# GILBERT.net
KiCad netlist of a schematic drawn in Altium Designer
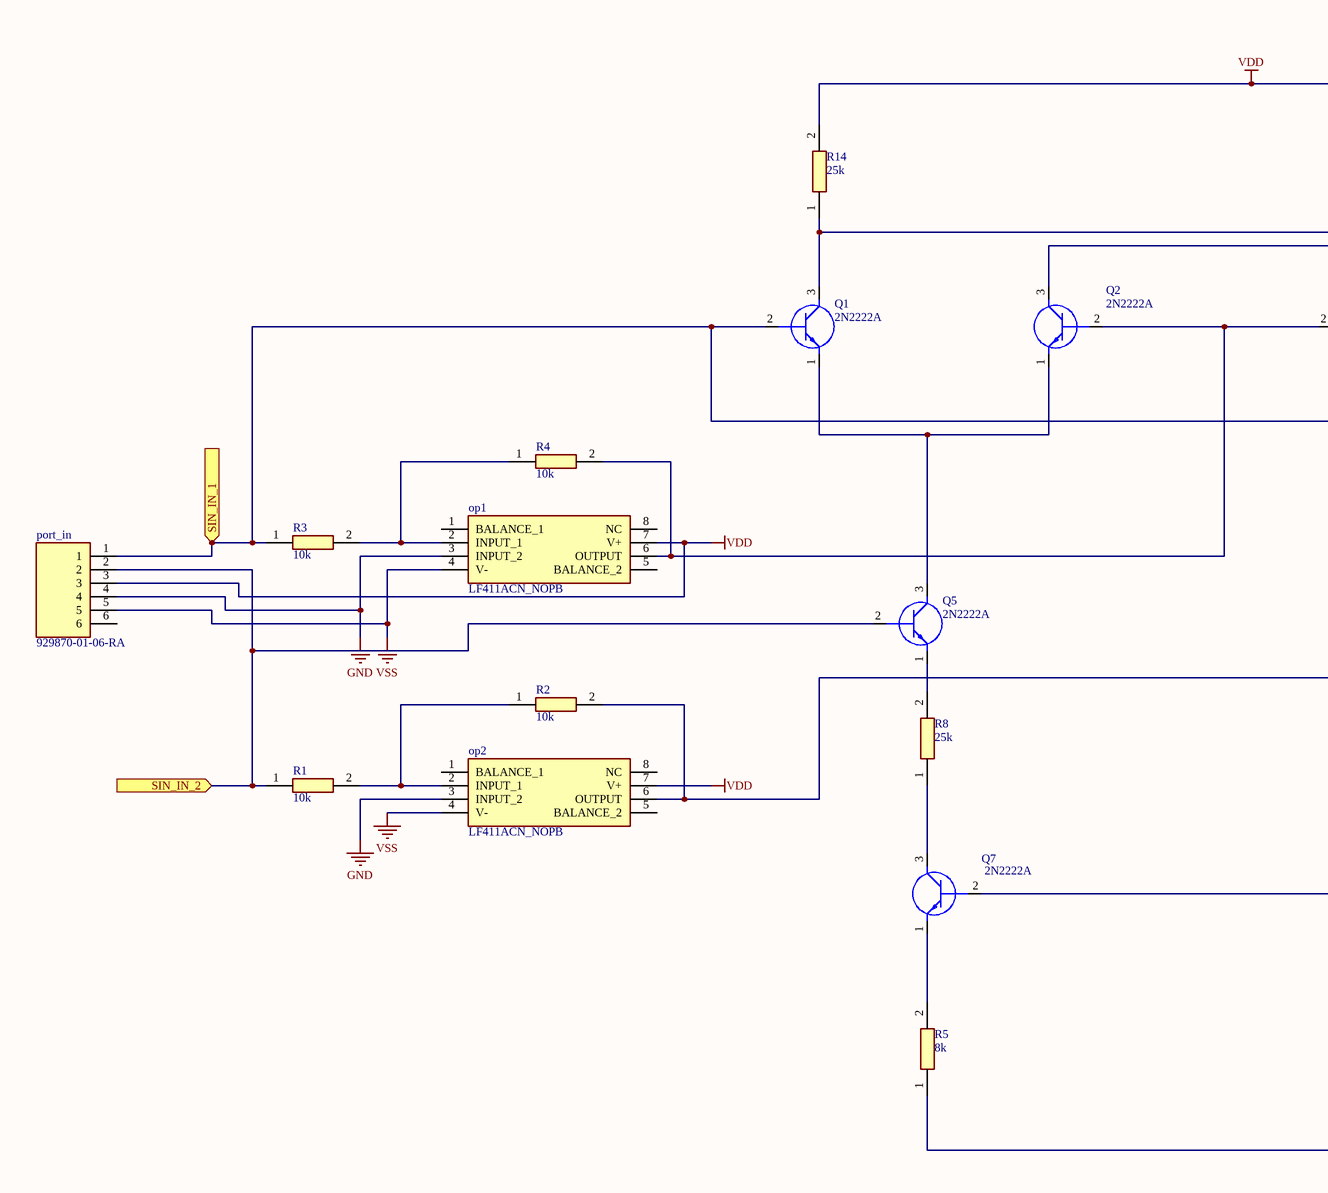
[diagram p0: GILBERT.SchDoc, left]
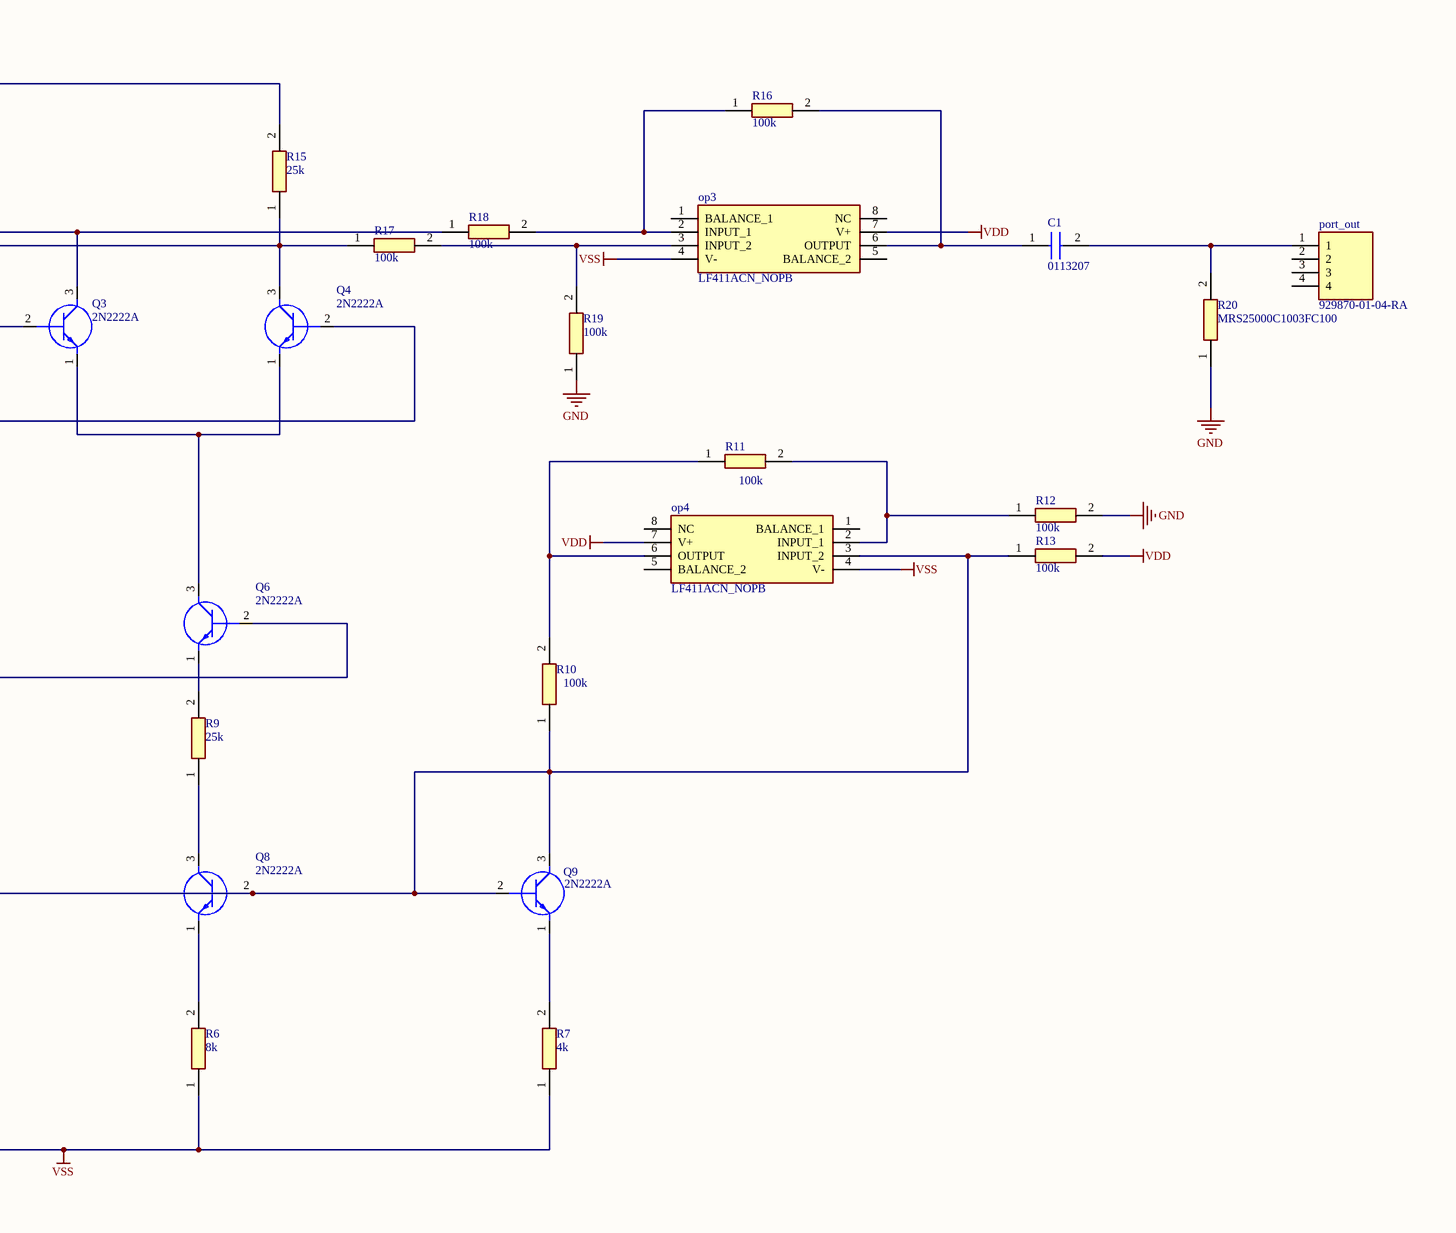
[diagram p1: GILBERT.SchDoc, right]

(export (version "E")
  (design (tool "Eeschema 10.0.6"))
  (components
    (comp (ref "C1")
      (value "0113207")
      (footprint "SamacSys:CAPPA2400W30L800D400")
      (description "Capacitor")
      (libsource (lib "SamacSys") (part "0113207"))
    )
    (comp (ref "op1")
      (value "LF411ACN_NOPB")
      (footprint "SamacSys:DIP794W53P254L959H508Q8N")
      (description "Integrated Circuit")
      (fields
        (field (name "MANUFACTURER_PART_NUMBER") "LF411ACN/NOPB")
        (field (name "MOUSER PART NUMBER") "926-LF411ACN/NOPB")
      )
      (libsource (lib "*") (part "LF411ACN_NOPB"))
    )
    (comp (ref "op2")
      (value "LF411ACN_NOPB")
      (footprint "SamacSys:DIP794W53P254L959H508Q8N")
      (description "Integrated Circuit")
      (fields
        (field (name "MANUFACTURER_PART_NUMBER") "LF411ACN/NOPB")
        (field (name "MOUSER PART NUMBER") "926-LF411ACN/NOPB")
      )
      (libsource (lib "SamacSys") (part "LF411ACN_NOPB"))
    )
    (comp (ref "op3")
      (value "LF411ACN_NOPB")
      (footprint "SamacSys:DIP794W53P254L959H508Q8N")
      (description "Integrated Circuit")
      (fields
        (field (name "MANUFACTURER_PART_NUMBER") "LF411ACN/NOPB")
        (field (name "MOUSER PART NUMBER") "926-LF411ACN/NOPB")
      )
      (libsource (lib "SamacSys") (part "LF411ACN_NOPB"))
    )
    (comp (ref "op4")
      (value "LF411ACN_NOPB")
      (footprint "SamacSys:DIP794W53P254L959H508Q8N")
      (description "Integrated Circuit")
      (fields
        (field (name "MANUFACTURER_PART_NUMBER") "LF411ACN/NOPB")
        (field (name "MOUSER PART NUMBER") "926-LF411ACN/NOPB")
      )
      (libsource (lib "") (part "LF411ACN_NOPB_1"))
    )
    (comp (ref "port_in")
      (value "929870-01-06-RA")
      (footprint "SamacSys:RHDR6W64P0X254_1X6_1524X254X380P")
      (description "Connector")
      (fields (field (name "MOUSER PART NUMBER") "517-929870-01-06-RA"))
      (libsource (lib "SamacSys") (part "929870-01-06-RA"))
    )
    (comp (ref "port_out")
      (value "929870-01-04-RA")
      (footprint "SamacSys:RHDR4W76P0X254_1X4_1016X254X826P")
      (description "Connector")
      (fields (field (name "MOUSER PART NUMBER") "517-929870-01-04-RA"))
      (libsource (lib "SamacSys") (part "929870-01-04-RA"))
    )
    (comp (ref "Q1")
      (value "2N2222A")
      (footprint "SamacSys:CENTRAL_TO18")
      (description "Transistor BJT NPN")
      (fields (field (name "MOUSER PART NUMBER") "610-2N2222A"))
      (libsource (lib "SamacSys") (part "2N2222A"))
    )
    (comp (ref "Q2")
      (value "2N2222A")
      (footprint "SamacSys:CENTRAL_TO18")
      (description "Transistor BJT NPN")
      (fields (field (name "MOUSER PART NUMBER") "610-2N2222A"))
      (libsource (lib "SamacSys") (part "2N2222A"))
    )
    (comp (ref "Q3")
      (value "2N2222A")
      (footprint "SamacSys:CENTRAL_TO18")
      (description "Transistor BJT NPN")
      (fields (field (name "MOUSER PART NUMBER") "610-2N2222A"))
      (libsource (lib "SamacSys") (part "2N2222A"))
    )
    (comp (ref "Q4")
      (value "2N2222A")
      (footprint "SamacSys:CENTRAL_TO18")
      (description "Transistor BJT NPN")
      (fields (field (name "MOUSER PART NUMBER") "610-2N2222A"))
      (libsource (lib "SamacSys") (part "2N2222A"))
    )
    (comp (ref "Q5")
      (value "2N2222A")
      (footprint "SamacSys:CENTRAL_TO18")
      (description "Transistor BJT NPN")
      (fields (field (name "MOUSER PART NUMBER") "610-2N2222A"))
      (libsource (lib "SamacSys") (part "2N2222A"))
    )
    (comp (ref "Q6")
      (value "2N2222A")
      (footprint "SamacSys:CENTRAL_TO18")
      (description "Transistor BJT NPN")
      (fields (field (name "MOUSER PART NUMBER") "610-2N2222A"))
      (libsource (lib "SamacSys") (part "2N2222A"))
    )
    (comp (ref "Q7")
      (value "2N2222A")
      (footprint "SamacSys:CENTRAL_TO18")
      (description "Transistor BJT NPN")
      (fields (field (name "MOUSER PART NUMBER") "610-2N2222A"))
      (libsource (lib "SamacSys") (part "2N2222A"))
    )
    (comp (ref "Q8")
      (value "2N2222A")
      (footprint "SamacSys:CENTRAL_TO18")
      (description "Transistor BJT NPN")
      (fields (field (name "MOUSER PART NUMBER") "610-2N2222A"))
      (libsource (lib "SamacSys") (part "2N2222A"))
    )
    (comp (ref "Q9")
      (value "2N2222A")
      (footprint "SamacSys:CENTRAL_TO18")
      (description "Transistor BJT NPN")
      (fields (field (name "MOUSER PART NUMBER") "610-2N2222A"))
      (libsource (lib "SamacSys") (part "2N2222A"))
    )
    (comp (ref "R1")
      (value "10k")
      (footprint "SamacSys:RESAD1650W60L650D250")
      (description "Resistor")
      (fields
        (field (name "MANUFACTURER_PART_NUMBER") "MRS25000C1003FC100")
        (field (name "MOUSER PART NUMBER") "594-MRS25000C1003FC1")
      )
      (libsource (lib "SamacSys") (part "MRS25000C1003FC100"))
    )
    (comp (ref "R2")
      (value "10k")
      (footprint "SamacSys:RESAD1650W60L650D250")
      (description "Resistor")
      (fields
        (field (name "MANUFACTURER_PART_NUMBER") "MRS25000C1003FC100")
        (field (name "MOUSER PART NUMBER") "594-MRS25000C1003FC1")
      )
      (libsource (lib "SamacSys") (part "MRS25000C1003FC100"))
    )
    (comp (ref "R3")
      (value "10k")
      (footprint "SamacSys:RESAD1650W60L650D250")
      (description "Resistor")
      (fields
        (field (name "MANUFACTURER_PART_NUMBER") "MRS25000C1003FC100")
        (field (name "MOUSER PART NUMBER") "594-MRS25000C1003FC1")
      )
      (libsource (lib "SamacSys") (part "MRS25000C1003FC100"))
    )
    (comp (ref "R4")
      (value "10k")
      (footprint "SamacSys:RESAD1650W60L650D250")
      (description "Resistor")
      (fields
        (field (name "MANUFACTURER_PART_NUMBER") "MRS25000C1003FC100")
        (field (name "MOUSER PART NUMBER") "594-MRS25000C1003FC1")
      )
      (libsource (lib "SamacSys") (part "MRS25000C1003FC100"))
    )
    (comp (ref "R5")
      (value "8k")
      (footprint "SamacSys:RESAD1650W60L650D250")
      (description "Resistor")
      (fields
        (field (name "MANUFACTURER_PART_NUMBER") "MRS25000C1003FC100")
        (field (name "MOUSER PART NUMBER") "594-MRS25000C1003FC1")
      )
      (libsource (lib "") (part "MRS25000C1003FC100_1"))
    )
    (comp (ref "R6")
      (value "8k")
      (footprint "SamacSys:RESAD1650W60L650D250")
      (description "Resistor")
      (fields
        (field (name "MANUFACTURER_PART_NUMBER") "MRS25000C1003FC100")
        (field (name "MOUSER PART NUMBER") "594-MRS25000C1003FC1")
      )
      (libsource (lib "") (part "MRS25000C1003FC100_1"))
    )
    (comp (ref "R7")
      (value "4k")
      (footprint "SamacSys:RESAD1650W60L650D250")
      (description "Resistor")
      (fields
        (field (name "MANUFACTURER_PART_NUMBER") "MRS25000C1003FC100")
        (field (name "MOUSER PART NUMBER") "594-MRS25000C1003FC1")
      )
      (libsource (lib "") (part "MRS25000C1003FC100_1"))
    )
    (comp (ref "R8")
      (value "25k")
      (footprint "SamacSys:RESAD1650W60L650D250")
      (description "Resistor")
      (fields
        (field (name "MANUFACTURER_PART_NUMBER") "MRS25000C1003FC100")
        (field (name "MOUSER PART NUMBER") "594-MRS25000C1003FC1")
      )
      (libsource (lib "") (part "MRS25000C1003FC100_1"))
    )
    (comp (ref "R9")
      (value "25k")
      (footprint "SamacSys:RESAD1650W60L650D250")
      (description "Resistor")
      (fields
        (field (name "MANUFACTURER_PART_NUMBER") "MRS25000C1003FC100")
        (field (name "MOUSER PART NUMBER") "594-MRS25000C1003FC1")
      )
      (libsource (lib "") (part "MRS25000C1003FC100_1"))
    )
    (comp (ref "R10")
      (value "100k")
      (footprint "SamacSys:RESAD1650W60L650D250")
      (description "Resistor")
      (fields
        (field (name "MANUFACTURER_PART_NUMBER") "MRS25000C1003FC100")
        (field (name "MOUSER PART NUMBER") "594-MRS25000C1003FC1")
      )
      (libsource (lib "") (part "MRS25000C1003FC100_1"))
    )
    (comp (ref "R11")
      (value "100k")
      (footprint "SamacSys:RESAD1650W60L650D250")
      (description "Resistor")
      (fields
        (field (name "MANUFACTURER_PART_NUMBER") "MRS25000C1003FC100")
        (field (name "MOUSER PART NUMBER") "594-MRS25000C1003FC1")
      )
      (libsource (lib "SamacSys") (part "MRS25000C1003FC100"))
    )
    (comp (ref "R12")
      (value "100k")
      (footprint "SamacSys:RESAD1650W60L650D250")
      (description "Resistor")
      (fields
        (field (name "MANUFACTURER_PART_NUMBER") "MRS25000C1003FC100")
        (field (name "MOUSER PART NUMBER") "594-MRS25000C1003FC1")
      )
      (libsource (lib "SamacSys") (part "MRS25000C1003FC100"))
    )
    (comp (ref "R13")
      (value "100k")
      (footprint "SamacSys:RESAD1650W60L650D250")
      (description "Resistor")
      (fields
        (field (name "MANUFACTURER_PART_NUMBER") "MRS25000C1003FC100")
        (field (name "MOUSER PART NUMBER") "594-MRS25000C1003FC1")
      )
      (libsource (lib "SamacSys") (part "MRS25000C1003FC100"))
    )
    (comp (ref "R14")
      (value "25k")
      (footprint "SamacSys:RESAD1650W60L650D250")
      (description "Resistor")
      (fields
        (field (name "MANUFACTURER_PART_NUMBER") "MRS25000C1003FC100")
        (field (name "MOUSER PART NUMBER") "594-MRS25000C1003FC1")
      )
      (libsource (lib "") (part "MRS25000C1003FC100_1"))
    )
    (comp (ref "R15")
      (value "25k")
      (footprint "SamacSys:RESAD1650W60L650D250")
      (description "Resistor")
      (fields
        (field (name "MANUFACTURER_PART_NUMBER") "MRS25000C1003FC100")
        (field (name "MOUSER PART NUMBER") "594-MRS25000C1003FC1")
      )
      (libsource (lib "") (part "MRS25000C1003FC100_1"))
    )
    (comp (ref "R16")
      (value "100k")
      (footprint "SamacSys:RESAD1650W60L650D250")
      (description "Resistor")
      (fields
        (field (name "MANUFACTURER_PART_NUMBER") "MRS25000C1003FC100")
        (field (name "MOUSER PART NUMBER") "594-MRS25000C1003FC1")
      )
      (libsource (lib "SamacSys") (part "MRS25000C1003FC100"))
    )
    (comp (ref "R17")
      (value "100k")
      (footprint "SamacSys:RESAD1650W60L650D250")
      (description "Resistor")
      (fields
        (field (name "MANUFACTURER_PART_NUMBER") "MRS25000C1003FC100")
        (field (name "MOUSER PART NUMBER") "594-MRS25000C1003FC1")
      )
      (libsource (lib "SamacSys") (part "MRS25000C1003FC100"))
    )
    (comp (ref "R18")
      (value "100k")
      (footprint "SamacSys:RESAD1650W60L650D250")
      (description "Resistor")
      (fields
        (field (name "MANUFACTURER_PART_NUMBER") "MRS25000C1003FC100")
        (field (name "MOUSER PART NUMBER") "594-MRS25000C1003FC1")
      )
      (libsource (lib "SamacSys") (part "MRS25000C1003FC100"))
    )
    (comp (ref "R19")
      (value "100k")
      (footprint "SamacSys:RESAD1650W60L650D250")
      (description "Resistor")
      (fields
        (field (name "MANUFACTURER_PART_NUMBER") "MRS25000C1003FC100")
        (field (name "MOUSER PART NUMBER") "594-MRS25000C1003FC1")
      )
      (libsource (lib "") (part "MRS25000C1003FC100_1"))
    )
    (comp (ref "R20")
      (value "MRS25000C1003FC100")
      (footprint "SamacSys:RESAD1650W60L650D250")
      (description "Resistor")
      (fields (field (name "MOUSER PART NUMBER") "594-MRS25000C1003FC1"))
      (libsource (lib "") (part "MRS25000C1003FC100_1"))
    )
  )
  (nets
    (net (code "1") (name "/SIN_IN_1") (class "Default")
      (node (ref "Q1") (pin "2") (pinfunction "B_2") (pintype "passive"))
      (node (ref "Q4") (pin "2") (pinfunction "B_2") (pintype "passive"))
      (node (ref "R3") (pin "1") (pinfunction "1_1") (pintype "passive"))
      (node (ref "port_in") (pin "1") (pinfunction "1_1") (pintype "passive"))
    )
    (net (code "2") (name "/SIN_IN_2") (class "Default")
      (node (ref "Q5") (pin "2") (pinfunction "B_2") (pintype "passive"))
      (node (ref "R1") (pin "1") (pinfunction "1_1") (pintype "passive"))
      (node (ref "port_in") (pin "2") (pinfunction "2_2") (pintype "passive"))
    )
    (net (code "3") (name "GND") (class "Default")
      (node (ref "R12") (pin "2") (pinfunction "2_2") (pintype "passive"))
      (node (ref "R19") (pin "1") (pinfunction "1_1") (pintype "passive"))
      (node (ref "R20") (pin "1") (pinfunction "1_1") (pintype "passive"))
      (node (ref "op1") (pin "3") (pinfunction "INPUT_2_3") (pintype "passive"))
      (node (ref "op2") (pin "3") (pinfunction "INPUT_2_3") (pintype "passive"))
      (node (ref "port_in") (pin "4") (pinfunction "4_4") (pintype "passive"))
    )
    (net (code "4") (name "Net-(C1-+)") (class "Default")
      (node (ref "C1") (pin "1") (pinfunction "+_1") (pintype "passive"))
      (node (ref "R16") (pin "2") (pinfunction "2_2") (pintype "passive"))
      (node (ref "op3") (pin "6") (pinfunction "OUTPUT_6") (pintype "passive"))
    )
    (net (code "5") (name "Net-(C1--)") (class "Default")
      (node (ref "C1") (pin "2") (pinfunction "-_2") (pintype "passive"))
      (node (ref "R20") (pin "2") (pinfunction "2_2") (pintype "passive"))
      (node (ref "port_out") (pin "1") (pinfunction "1_1") (pintype "passive"))
    )
    (net (code "6") (name "Net-(Q1-C)") (class "Default")
      (node (ref "Q1") (pin "3") (pinfunction "C_3") (pintype "passive"))
      (node (ref "Q3") (pin "3") (pinfunction "C_3") (pintype "passive"))
      (node (ref "R14") (pin "1") (pinfunction "1_1") (pintype "passive"))
      (node (ref "R18") (pin "1") (pinfunction "1_1") (pintype "passive"))
    )
    (net (code "7") (name "Net-(Q1-E)") (class "Default")
      (node (ref "Q1") (pin "1") (pinfunction "E_1") (pintype "passive"))
      (node (ref "Q2") (pin "1") (pinfunction "E_1") (pintype "passive"))
      (node (ref "Q5") (pin "3") (pinfunction "C_3") (pintype "passive"))
    )
    (net (code "8") (name "Net-(Q2-B)") (class "Default")
      (node (ref "Q2") (pin "2") (pinfunction "B_2") (pintype "passive"))
      (node (ref "Q3") (pin "2") (pinfunction "B_2") (pintype "passive"))
      (node (ref "R4") (pin "2") (pinfunction "2_2") (pintype "passive"))
      (node (ref "op1") (pin "6") (pinfunction "OUTPUT_6") (pintype "passive"))
    )
    (net (code "9") (name "Net-(Q2-C)") (class "Default")
      (node (ref "Q2") (pin "3") (pinfunction "C_3") (pintype "passive"))
      (node (ref "Q4") (pin "3") (pinfunction "C_3") (pintype "passive"))
      (node (ref "R15") (pin "1") (pinfunction "1_1") (pintype "passive"))
      (node (ref "R17") (pin "1") (pinfunction "1_1") (pintype "passive"))
    )
    (net (code "10") (name "Net-(Q3-E)") (class "Default")
      (node (ref "Q3") (pin "1") (pinfunction "E_1") (pintype "passive"))
      (node (ref "Q4") (pin "1") (pinfunction "E_1") (pintype "passive"))
      (node (ref "Q6") (pin "3") (pinfunction "C_3") (pintype "passive"))
    )
    (net (code "11") (name "Net-(Q5-E)") (class "Default")
      (node (ref "Q5") (pin "1") (pinfunction "E_1") (pintype "passive"))
      (node (ref "R8") (pin "2") (pinfunction "2_2") (pintype "passive"))
    )
    (net (code "12") (name "Net-(Q6-B)") (class "Default")
      (node (ref "Q6") (pin "2") (pinfunction "B_2") (pintype "passive"))
      (node (ref "R2") (pin "2") (pinfunction "2_2") (pintype "passive"))
      (node (ref "op2") (pin "6") (pinfunction "OUTPUT_6") (pintype "passive"))
    )
    (net (code "13") (name "Net-(Q6-E)") (class "Default")
      (node (ref "Q6") (pin "1") (pinfunction "E_1") (pintype "passive"))
      (node (ref "R9") (pin "2") (pinfunction "2_2") (pintype "passive"))
    )
    (net (code "14") (name "Net-(Q7-B)") (class "Default")
      (node (ref "Q7") (pin "2") (pinfunction "B_2") (pintype "passive"))
      (node (ref "Q8") (pin "2") (pinfunction "B_2") (pintype "passive"))
      (node (ref "Q9") (pin "2") (pinfunction "B_2") (pintype "passive"))
      (node (ref "Q9") (pin "3") (pinfunction "C_3") (pintype "passive"))
      (node (ref "R10") (pin "1") (pinfunction "1_1") (pintype "passive"))
      (node (ref "R13") (pin "1") (pinfunction "1_1") (pintype "passive"))
      (node (ref "op4") (pin "3") (pinfunction "INPUT_2_3") (pintype "passive"))
    )
    (net (code "15") (name "Net-(Q7-C)") (class "Default")
      (node (ref "Q7") (pin "3") (pinfunction "C_3") (pintype "passive"))
      (node (ref "R8") (pin "1") (pinfunction "1_1") (pintype "passive"))
    )
    (net (code "16") (name "Net-(Q7-E)") (class "Default")
      (node (ref "Q7") (pin "1") (pinfunction "E_1") (pintype "passive"))
      (node (ref "R5") (pin "2") (pinfunction "2_2") (pintype "passive"))
    )
    (net (code "17") (name "Net-(Q8-C)") (class "Default")
      (node (ref "Q8") (pin "3") (pinfunction "C_3") (pintype "passive"))
      (node (ref "R9") (pin "1") (pinfunction "1_1") (pintype "passive"))
    )
    (net (code "18") (name "Net-(Q8-E)") (class "Default")
      (node (ref "Q8") (pin "1") (pinfunction "E_1") (pintype "passive"))
      (node (ref "R6") (pin "2") (pinfunction "2_2") (pintype "passive"))
    )
    (net (code "19") (name "Net-(Q9-E)") (class "Default")
      (node (ref "Q9") (pin "1") (pinfunction "E_1") (pintype "passive"))
      (node (ref "R7") (pin "2") (pinfunction "2_2") (pintype "passive"))
    )
    (net (code "20") (name "Net-(op1-INPUT_1)") (class "Default")
      (node (ref "R3") (pin "2") (pinfunction "2_2") (pintype "passive"))
      (node (ref "R4") (pin "1") (pinfunction "1_1") (pintype "passive"))
      (node (ref "op1") (pin "2") (pinfunction "INPUT_1_2") (pintype "passive"))
    )
    (net (code "21") (name "Net-(op2-INPUT_1)") (class "Default")
      (node (ref "R1") (pin "2") (pinfunction "2_2") (pintype "passive"))
      (node (ref "R2") (pin "1") (pinfunction "1_1") (pintype "passive"))
      (node (ref "op2") (pin "2") (pinfunction "INPUT_1_2") (pintype "passive"))
    )
    (net (code "22") (name "Net-(op3-INPUT_1)") (class "Default")
      (node (ref "R16") (pin "1") (pinfunction "1_1") (pintype "passive"))
      (node (ref "R18") (pin "2") (pinfunction "2_2") (pintype "passive"))
      (node (ref "op3") (pin "2") (pinfunction "INPUT_1_2") (pintype "passive"))
    )
    (net (code "23") (name "Net-(op3-INPUT_2)") (class "Default")
      (node (ref "R17") (pin "2") (pinfunction "2_2") (pintype "passive"))
      (node (ref "R19") (pin "2") (pinfunction "2_2") (pintype "passive"))
      (node (ref "op3") (pin "3") (pinfunction "INPUT_2_3") (pintype "passive"))
    )
    (net (code "24") (name "Net-(op4-INPUT_1)") (class "Default")
      (node (ref "R11") (pin "2") (pinfunction "2_2") (pintype "passive"))
      (node (ref "R12") (pin "1") (pinfunction "1_1") (pintype "passive"))
      (node (ref "op4") (pin "2") (pinfunction "INPUT_1_2") (pintype "passive"))
    )
    (net (code "25") (name "Net-(op4-OUTPUT)") (class "Default")
      (node (ref "R10") (pin "2") (pinfunction "2_2") (pintype "passive"))
      (node (ref "R11") (pin "1") (pinfunction "1_1") (pintype "passive"))
      (node (ref "op4") (pin "6") (pinfunction "OUTPUT_6") (pintype "passive"))
    )
    (net (code "26") (name "VDD") (class "Default")
      (node (ref "R13") (pin "2") (pinfunction "2_2") (pintype "passive"))
      (node (ref "R14") (pin "2") (pinfunction "2_2") (pintype "passive"))
      (node (ref "R15") (pin "2") (pinfunction "2_2") (pintype "passive"))
      (node (ref "op1") (pin "7") (pinfunction "V+_7") (pintype "passive"))
      (node (ref "op2") (pin "7") (pinfunction "V+_7") (pintype "passive"))
      (node (ref "op3") (pin "7") (pinfunction "V+_7") (pintype "passive"))
      (node (ref "op4") (pin "7") (pinfunction "V+_7") (pintype "passive"))
      (node (ref "port_in") (pin "3") (pinfunction "3_3") (pintype "passive"))
    )
    (net (code "27") (name "VSS") (class "Default")
      (node (ref "R5") (pin "1") (pinfunction "1_1") (pintype "passive"))
      (node (ref "R6") (pin "1") (pinfunction "1_1") (pintype "passive"))
      (node (ref "R7") (pin "1") (pinfunction "1_1") (pintype "passive"))
      (node (ref "op1") (pin "4") (pinfunction "V-_4") (pintype "passive"))
      (node (ref "op2") (pin "4") (pinfunction "V-_4") (pintype "passive"))
      (node (ref "op3") (pin "4") (pinfunction "V-_4") (pintype "passive"))
      (node (ref "op4") (pin "4") (pinfunction "V-_4") (pintype "passive"))
      (node (ref "port_in") (pin "5") (pinfunction "5_5") (pintype "passive"))
    )
    (net (code "28") (name "unconnected-(op1-BALANCE_1-Pad1)") (class "Default")
      (node (ref "op1") (pin "1") (pinfunction "BALANCE_1_1") (pintype "passive"))
    )
    (net (code "29") (name "unconnected-(op1-BALANCE_2-Pad5)") (class "Default")
      (node (ref "op1") (pin "5") (pinfunction "BALANCE_2_5") (pintype "passive"))
    )
    (net (code "30") (name "unconnected-(op1-NC-Pad8)") (class "Default")
      (node (ref "op1") (pin "8") (pinfunction "NC_8") (pintype "passive"))
    )
    (net (code "31") (name "unconnected-(op2-BALANCE_1-Pad1)") (class "Default")
      (node (ref "op2") (pin "1") (pinfunction "BALANCE_1_1") (pintype "passive"))
    )
    (net (code "32") (name "unconnected-(op2-BALANCE_2-Pad5)") (class "Default")
      (node (ref "op2") (pin "5") (pinfunction "BALANCE_2_5") (pintype "passive"))
    )
    (net (code "33") (name "unconnected-(op2-NC-Pad8)") (class "Default")
      (node (ref "op2") (pin "8") (pinfunction "NC_8") (pintype "passive"))
    )
    (net (code "34") (name "unconnected-(op3-BALANCE_1-Pad1)") (class "Default")
      (node (ref "op3") (pin "1") (pinfunction "BALANCE_1_1") (pintype "passive"))
    )
    (net (code "35") (name "unconnected-(op3-BALANCE_2-Pad5)") (class "Default")
      (node (ref "op3") (pin "5") (pinfunction "BALANCE_2_5") (pintype "passive"))
    )
    (net (code "36") (name "unconnected-(op3-NC-Pad8)") (class "Default")
      (node (ref "op3") (pin "8") (pinfunction "NC_8") (pintype "passive"))
    )
    (net (code "37") (name "unconnected-(op4-BALANCE_1-Pad1)") (class "Default")
      (node (ref "op4") (pin "1") (pinfunction "BALANCE_1_1") (pintype "passive"))
    )
    (net (code "38") (name "unconnected-(op4-BALANCE_2-Pad5)") (class "Default")
      (node (ref "op4") (pin "5") (pinfunction "BALANCE_2_5") (pintype "passive"))
    )
    (net (code "39") (name "unconnected-(op4-NC-Pad8)") (class "Default")
      (node (ref "op4") (pin "8") (pinfunction "NC_8") (pintype "passive"))
    )
    (net (code "40") (name "unconnected-(port_in-Pad6)") (class "Default")
      (node (ref "port_in") (pin "6") (pinfunction "6_6") (pintype "passive"))
    )
    (net (code "41") (name "unconnected-(port_out-Pad2)") (class "Default")
      (node (ref "port_out") (pin "2") (pinfunction "2_2") (pintype "passive"))
    )
    (net (code "42") (name "unconnected-(port_out-Pad3)") (class "Default")
      (node (ref "port_out") (pin "3") (pinfunction "3_3") (pintype "passive"))
    )
    (net (code "43") (name "unconnected-(port_out-Pad4)") (class "Default")
      (node (ref "port_out") (pin "4") (pinfunction "4_4") (pintype "passive"))
    )
  )
)
